# Sheet1.net
KiCad netlist of a schematic drawn in Altium Designer
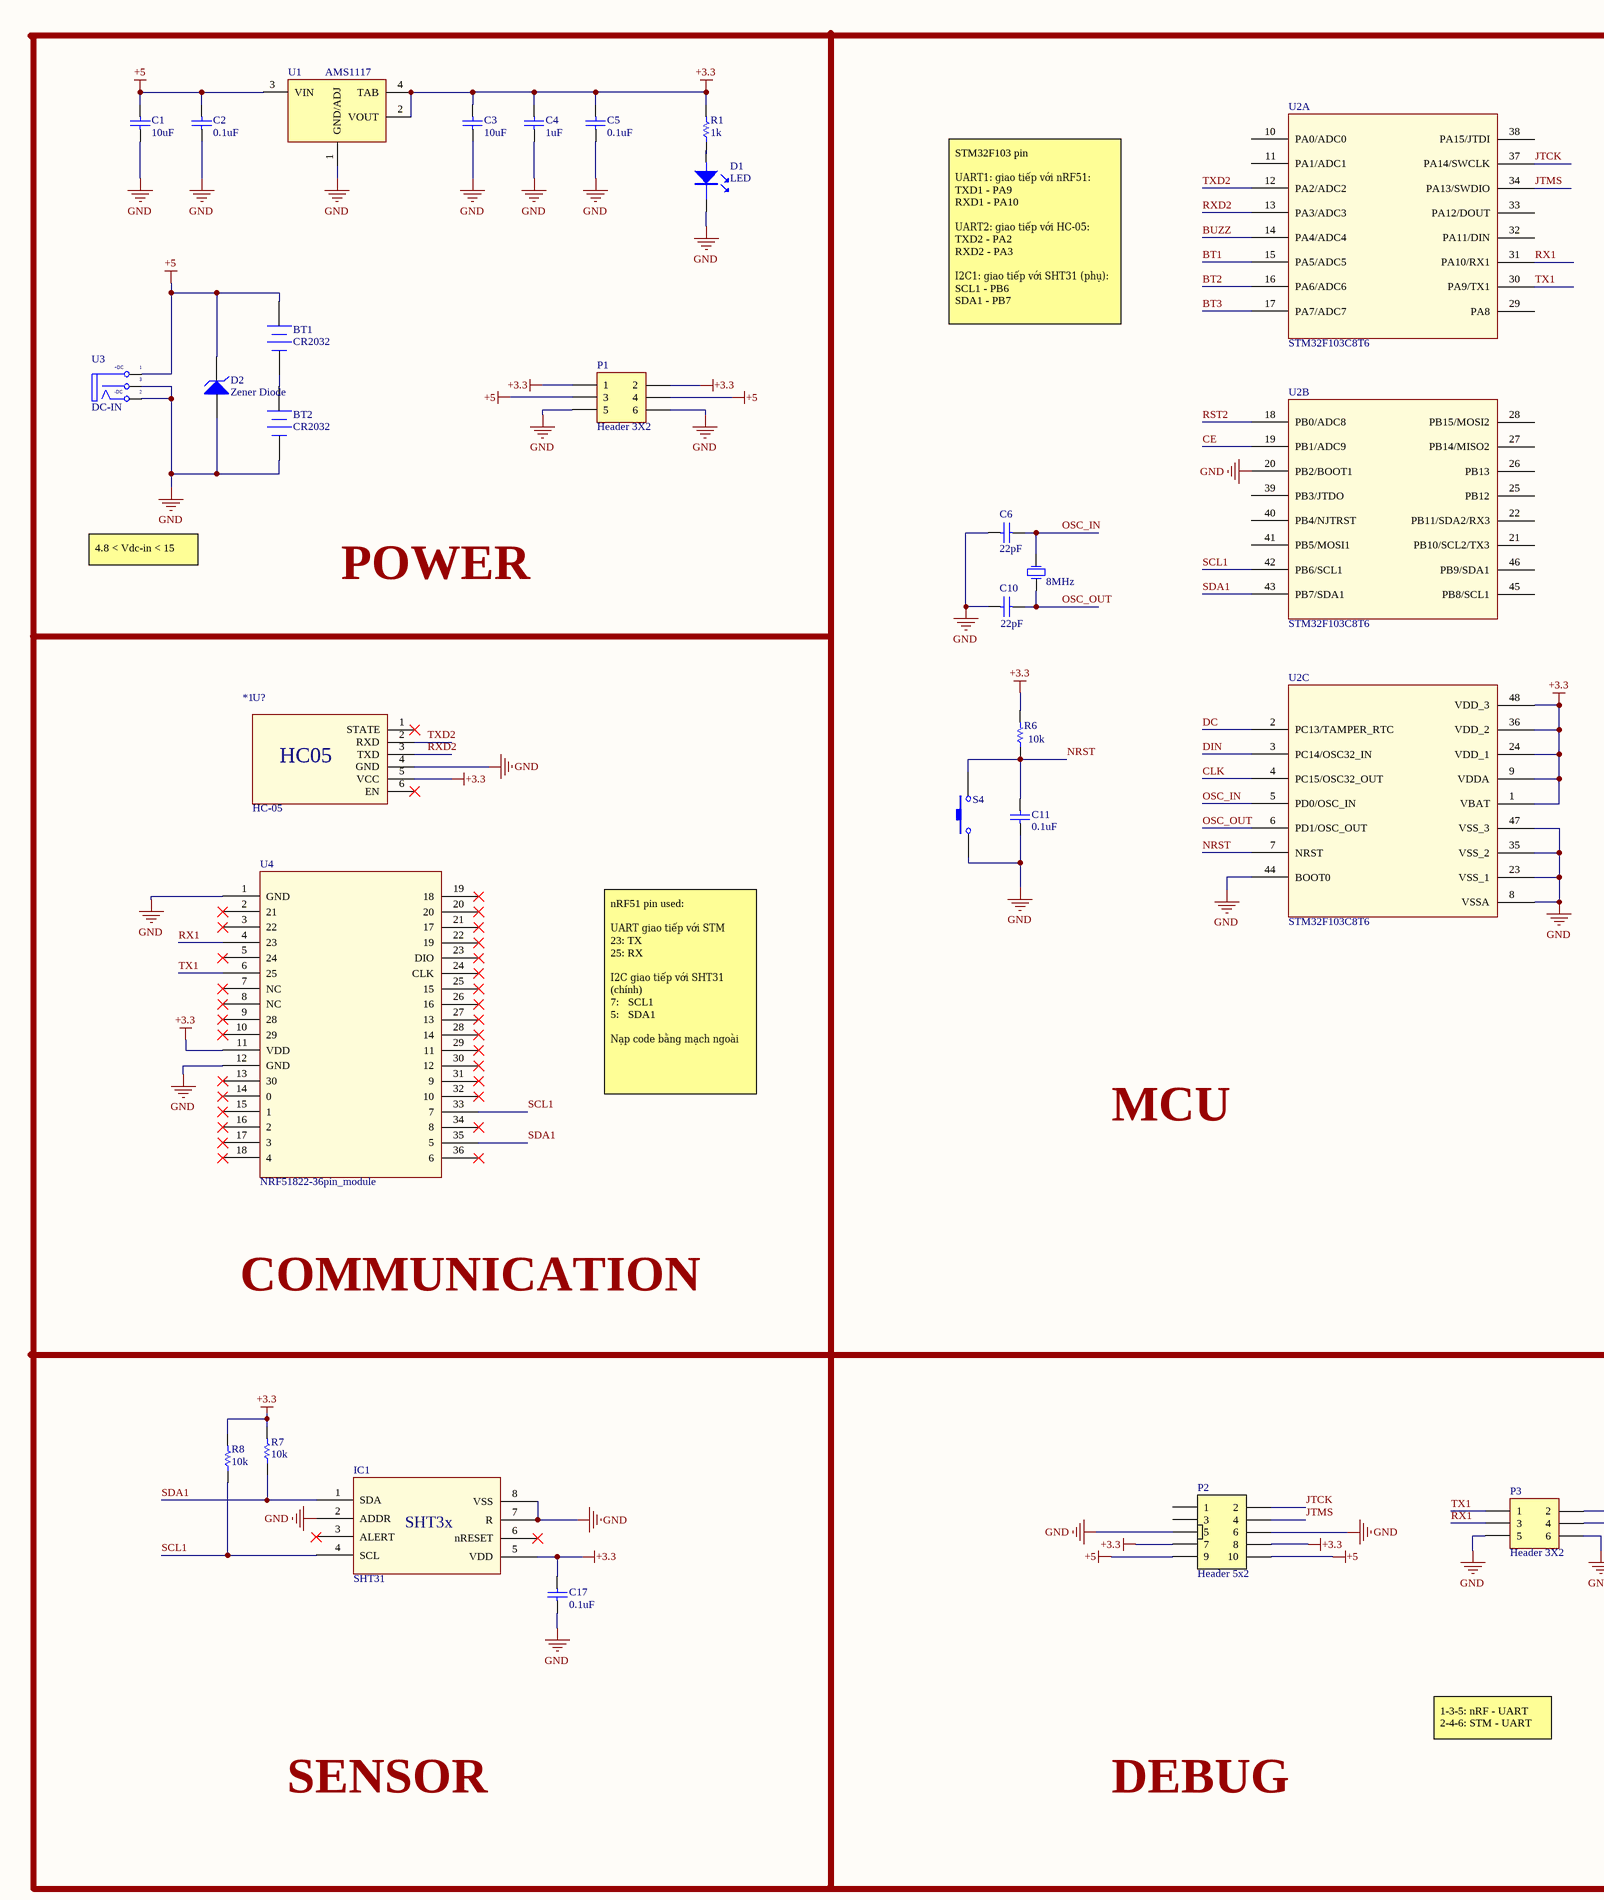
[diagram p0: Sheet1.SchDoc, left]
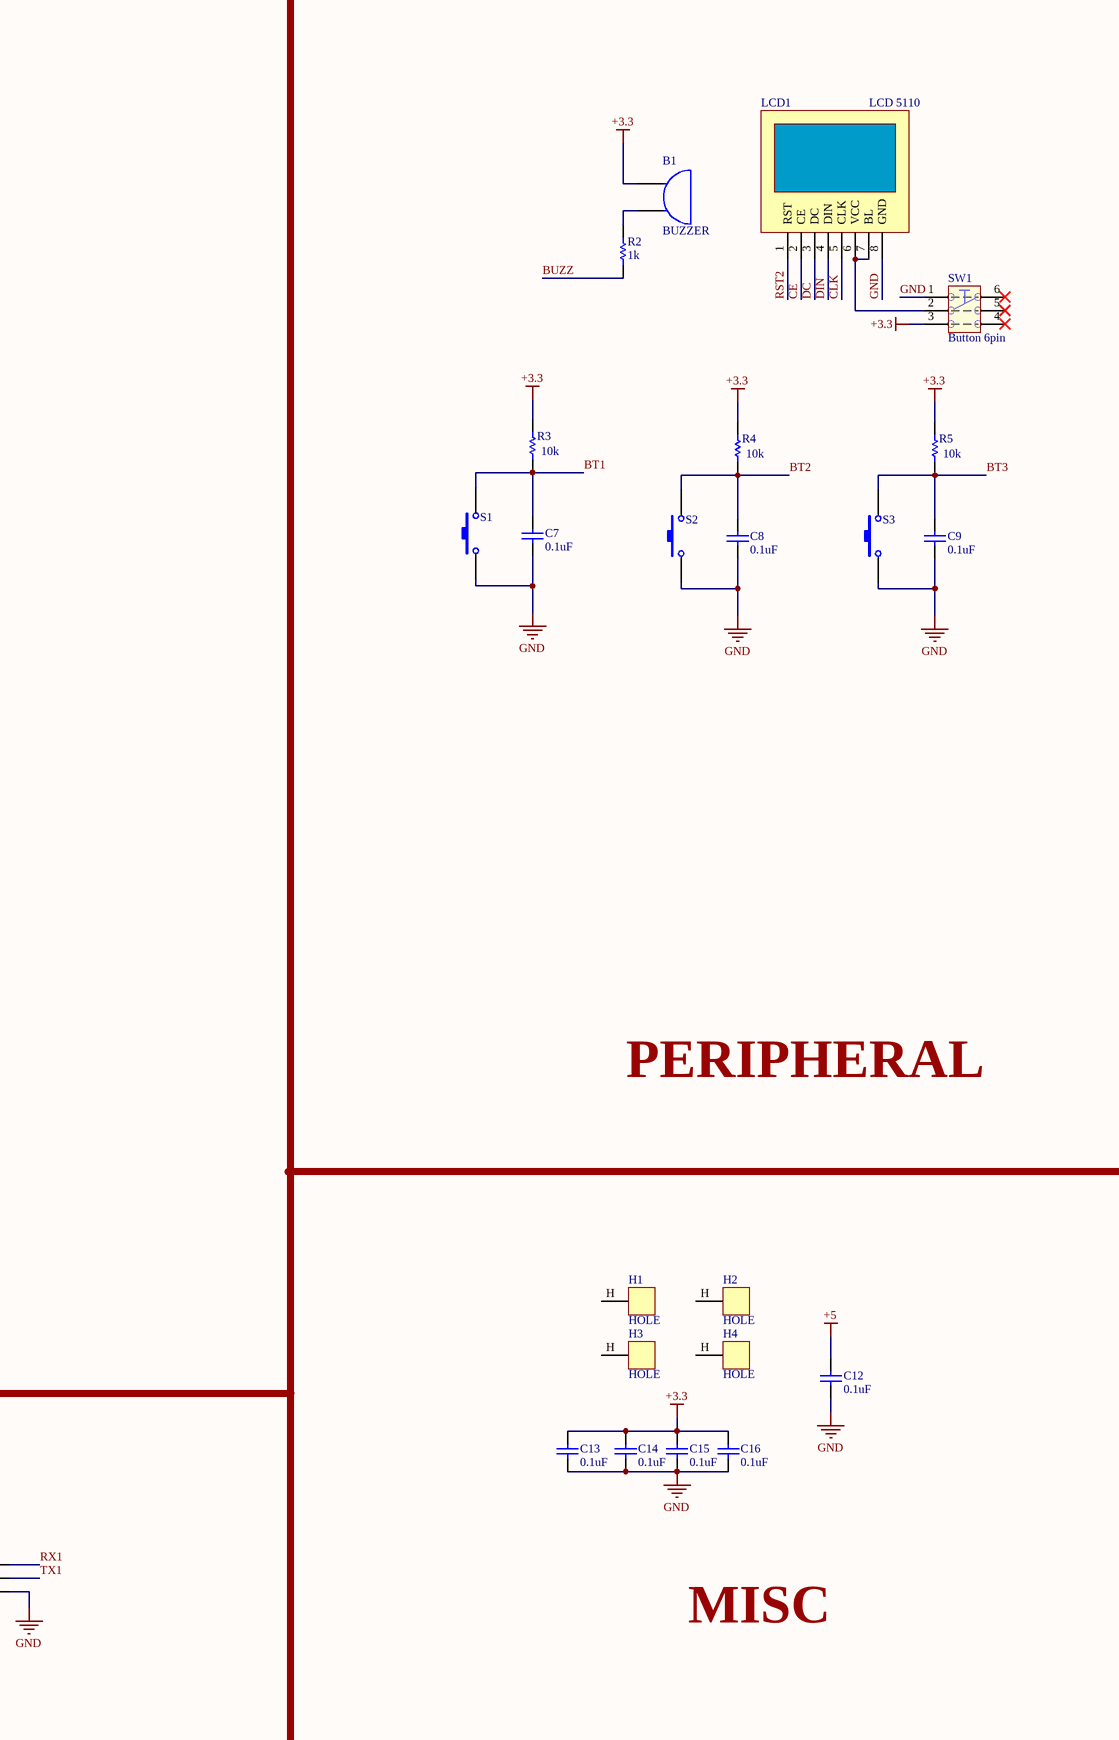
[diagram p1: Sheet1.SchDoc, right]

(export (version "E")
  (design (tool "Eeschema 10.0.6"))
  (components
    (comp (ref "*1") (value "HC-05") (footprint "HC-05") (libsource (lib "DucNam") (part "HC-05")))
    (comp (ref "B1")
      (value "BUZZER")
      (footprint "SPEAKER")
      (libsource (lib "ThinhNguyenLib") (part "BUZZER"))
    )
    (comp (ref "BT1")
      (value "CR2032")
      (footprint "PIN3V")
      (description "Multicell Battery")
      (fields (field (name "PUBLISHER") "Altium Limited"))
      (libsource (lib "DoHuong_sch") (part "Battery"))
    )
    (comp (ref "BT2")
      (value "CR2032")
      (footprint "PIN3V")
      (description "Multicell Battery")
      (fields (field (name "PUBLISHER") "Altium Limited"))
      (libsource (lib "DoHuong_sch") (part "Battery"))
    )
    (comp (ref "C1")
      (value "10uF")
      (footprint "C0805")
      (description "CAP CER 10UF 16V X7R 0805")
      (fields
        (field (name "PARTNUMBER") "EMK212BB7106MG-T")
        (field (name "TOLERANCE") "±20%")
        (field (name "CREATOR") "Quyen.nv")
      )
      (libsource (lib "MKP_lib") (part "CAP"))
    )
    (comp (ref "C2")
      (value "0.1uF")
      (footprint "C0805")
      (description "CAP CER 0.1UF 16V X7R 0805")
      (fields
        (field (name "PARTNUMBER") "C0805C104K4RACTU")
        (field (name "TOLERANCE") "±10%")
        (field (name "CREATOR") "Tunn")
      )
      (libsource (lib "MKP_lib") (part "CAP"))
    )
    (comp (ref "C3")
      (value "10uF")
      (footprint "C0805")
      (description "CAP CER 10UF 16V X7R 0805")
      (fields
        (field (name "PARTNUMBER") "EMK212BB7106MG-T")
        (field (name "TOLERANCE") "±20%")
        (field (name "CREATOR") "Quyen.nv")
      )
      (libsource (lib "MKP_lib") (part "CAP"))
    )
    (comp (ref "C4")
      (value "1uF")
      (footprint "C0805")
      (description "CAP CER 1UF 35V X7R 0805")
      (fields
        (field (name "PARTNUMBER") "GMK212B7105KG-T")
        (field (name "TOLERANCE") "±10%")
        (field (name "CREATOR") "Quyen.nv")
      )
      (libsource (lib "MKP_lib") (part "CAP"))
    )
    (comp (ref "C5")
      (value "0.1uF")
      (footprint "C0805")
      (description "CAP CER 0.1UF 16V X7R 0805")
      (fields
        (field (name "PARTNUMBER") "C0805C104K4RACTU")
        (field (name "TOLERANCE") "±10%")
        (field (name "CREATOR") "Tunn")
      )
      (libsource (lib "MKP_lib") (part "CAP"))
    )
    (comp (ref "C6")
      (value "22pF")
      (footprint "C0805")
      (description "CAP CER 0.22pF 0805")
      (fields
        (field (name "PARTNUMBER") "C0805C224K3RACAUTO")
        (field (name "TOLERANCE") "±10%")
        (field (name "CREATOR") "Quyen.nv")
      )
      (libsource (lib "MKP_lib") (part "CAP"))
    )
    (comp (ref "C7")
      (value "0.1uF")
      (footprint "C0805")
      (description "CAP CER 0.1UF 16V X7R 0805")
      (fields
        (field (name "PARTNUMBER") "C0805C104K4RACTU")
        (field (name "TOLERANCE") "±10%")
        (field (name "CREATOR") "Tunn")
      )
      (libsource (lib "MKP_lib") (part "CAP"))
    )
    (comp (ref "C8")
      (value "0.1uF")
      (footprint "C0805")
      (description "CAP CER 0.1UF 16V X7R 0805")
      (fields
        (field (name "PARTNUMBER") "C0805C104K4RACTU")
        (field (name "TOLERANCE") "±10%")
        (field (name "CREATOR") "Tunn")
      )
      (libsource (lib "MKP_lib") (part "CAP"))
    )
    (comp (ref "C9")
      (value "0.1uF")
      (footprint "C0805")
      (description "CAP CER 0.1UF 16V X7R 0805")
      (fields
        (field (name "PARTNUMBER") "C0805C104K4RACTU")
        (field (name "TOLERANCE") "±10%")
        (field (name "CREATOR") "Tunn")
      )
      (libsource (lib "MKP_lib") (part "CAP"))
    )
    (comp (ref "C10")
      (value "22pF")
      (footprint "C0805")
      (description "CAP CER 0.22pF 0805")
      (fields
        (field (name "PARTNUMBER") "C0805C224K3RACAUTO")
        (field (name "TOLERANCE") "±10%")
        (field (name "CREATOR") "Quyen.nv")
      )
      (libsource (lib "MKP_lib") (part "CAP"))
    )
    (comp (ref "C11")
      (value "0.1uF")
      (footprint "C0805")
      (description "CAP CER 0.1UF 16V X7R 0805")
      (fields
        (field (name "PARTNUMBER") "C0805C104K4RACTU")
        (field (name "TOLERANCE") "±10%")
        (field (name "CREATOR") "Tunn")
      )
      (libsource (lib "MKP_lib") (part "CAP"))
    )
    (comp (ref "C12")
      (value "0.1uF")
      (footprint "C0805")
      (description "CAP CER 0.1UF 16V X7R 0805")
      (fields
        (field (name "PARTNUMBER") "C0805C104K4RACTU")
        (field (name "TOLERANCE") "±10%")
        (field (name "CREATOR") "Tunn")
      )
      (libsource (lib "MKP_lib") (part "CAP"))
    )
    (comp (ref "C13")
      (value "0.1uF")
      (footprint "C0805")
      (description "CAP CER 0.1UF 16V X7R 0805")
      (fields
        (field (name "PARTNUMBER") "C0805C104K4RACTU")
        (field (name "TOLERANCE") "±10%")
        (field (name "CREATOR") "Tunn")
      )
      (libsource (lib "MKP_lib") (part "CAP"))
    )
    (comp (ref "C14")
      (value "0.1uF")
      (footprint "C0805")
      (description "CAP CER 0.1UF 16V X7R 0805")
      (fields
        (field (name "PARTNUMBER") "C0805C104K4RACTU")
        (field (name "TOLERANCE") "±10%")
        (field (name "CREATOR") "Tunn")
      )
      (libsource (lib "MKP_lib") (part "CAP"))
    )
    (comp (ref "C15")
      (value "0.1uF")
      (footprint "C0805")
      (description "CAP CER 0.1UF 16V X7R 0805")
      (fields
        (field (name "PARTNUMBER") "C0805C104K4RACTU")
        (field (name "TOLERANCE") "±10%")
        (field (name "CREATOR") "Tunn")
      )
      (libsource (lib "MKP_lib") (part "CAP"))
    )
    (comp (ref "C16")
      (value "0.1uF")
      (footprint "C0805")
      (description "CAP CER 0.1UF 16V X7R 0805")
      (fields
        (field (name "PARTNUMBER") "C0805C104K4RACTU")
        (field (name "TOLERANCE") "±10%")
        (field (name "CREATOR") "Tunn")
      )
      (libsource (lib "MKP_lib") (part "CAP"))
    )
    (comp (ref "C17")
      (value "0.1uF")
      (footprint "C0805")
      (description "CAP CER 0.1UF 16V X7R 0805")
      (fields
        (field (name "PARTNUMBER") "C0805C104K4RACTU")
        (field (name "TOLERANCE") "±10%")
        (field (name "CREATOR") "Tunn")
      )
      (libsource (lib "MKP_lib") (part "CAP"))
    )
    (comp (ref "D1") (value "LED") (footprint "LED SMD 0805") (libsource (lib "ThinhNguyenLib") (part "LED")))
    (comp (ref "D2")
      (value "Zener Diode")
      (footprint "Zener Diode")
      (description "General SCH for Zener Diode")
      (libsource (lib "DucNam") (part "Zener Diode"))
    )
    (comp (ref "H1") (value "HOLE") (footprint "HOLE") (libsource (lib "ThinhNguyenLib") (part "HOLE")))
    (comp (ref "H2") (value "HOLE") (footprint "HOLE") (libsource (lib "ThinhNguyenLib") (part "HOLE")))
    (comp (ref "H3") (value "HOLE") (footprint "HOLE") (libsource (lib "ThinhNguyenLib") (part "HOLE")))
    (comp (ref "H4") (value "HOLE") (footprint "HOLE") (libsource (lib "ThinhNguyenLib") (part "HOLE")))
    (comp (ref "IC1")
      (value "SHT31")
      (footprint "DFN-8")
      (description "Sensirion Humidity & Temperature Sensor")
      (libsource (lib "DucNam") (part "SHT31"))
    )
    (comp (ref "LCD1")
      (value "LCD 5110")
      (footprint "LCD 5110")
      (libsource (lib "ThinhNguyenLib") (part "LCD 5110"))
    )
    (comp (ref "P1")
      (value "Header 3X2")
      (footprint "HDR2X3")
      (description "Header, 3-Pin, Dual row")
      (fields (field (name "PUBLISHER") "Altium Limited"))
      (libsource (lib "DoHuong_sch") (part "Header 3X2"))
    )
    (comp (ref "P2")
      (value "Header 5x2")
      (footprint "Header 5x2 horizontal (2.54mm)")
      (description "Header 5x2 ,used for ST-Link")
      (libsource (lib "DucNam") (part "Header 5x2 (2.54mm)"))
    )
    (comp (ref "P3")
      (value "Header 3X2")
      (footprint "HDR2X3")
      (description "Header, 3-Pin, Dual row")
      (fields (field (name "PUBLISHER") "Altium Limited"))
      (libsource (lib "DoHuong_sch") (part "Header 3X2"))
    )
    (comp (ref "R1")
      (value "1k")
      (footprint "R0805")
      (description "RES SMD 100 OHM 1% 1/8W 0805")
      (fields
        (field (name "PARTNUMBER") "RC0805FR-07100RL")
        (field (name "TOLERANCE") "1%")
        (field (name "CREATOR") "Quyen.nv")
      )
      (libsource (lib "MKP_lib") (part "RES"))
    )
    (comp (ref "R2")
      (value "1k")
      (footprint "R0805")
      (description "RES SMD 100 OHM 1% 1/8W 0805")
      (fields
        (field (name "PARTNUMBER") "RC0805FR-07100RL")
        (field (name "TOLERANCE") "1%")
        (field (name "CREATOR") "Quyen.nv")
      )
      (libsource (lib "MKP_lib") (part "RES"))
    )
    (comp (ref "R3")
      (value "10k")
      (footprint "R0805")
      (description "RES SMD 100 OHM 1% 1/8W 0805")
      (fields
        (field (name "PARTNUMBER") "RC0805FR-07100RL")
        (field (name "TOLERANCE") "1%")
        (field (name "CREATOR") "Quyen.nv")
      )
      (libsource (lib "MKP_lib") (part "RES"))
    )
    (comp (ref "R4")
      (value "10k")
      (footprint "R0805")
      (description "RES SMD 100 OHM 1% 1/8W 0805")
      (fields
        (field (name "PARTNUMBER") "RC0805FR-07100RL")
        (field (name "TOLERANCE") "1%")
        (field (name "CREATOR") "Quyen.nv")
      )
      (libsource (lib "MKP_lib") (part "RES"))
    )
    (comp (ref "R5")
      (value "10k")
      (footprint "R0805")
      (description "RES SMD 100 OHM 1% 1/8W 0805")
      (fields
        (field (name "PARTNUMBER") "RC0805FR-07100RL")
        (field (name "TOLERANCE") "1%")
        (field (name "CREATOR") "Quyen.nv")
      )
      (libsource (lib "MKP_lib") (part "RES"))
    )
    (comp (ref "R6")
      (value "10k")
      (footprint "R0805")
      (description "RES SMD 100 OHM 1% 1/8W 0805")
      (fields
        (field (name "PARTNUMBER") "RC0805FR-07100RL")
        (field (name "TOLERANCE") "1%")
        (field (name "CREATOR") "Quyen.nv")
      )
      (libsource (lib "MKP_lib") (part "RES"))
    )
    (comp (ref "R7")
      (value "10k")
      (footprint "R0805")
      (description "RES SMD 100 OHM 1% 1/8W 0805")
      (fields
        (field (name "PARTNUMBER") "RC0805FR-07100RL")
        (field (name "TOLERANCE") "1%")
        (field (name "CREATOR") "Quyen.nv")
      )
      (libsource (lib "MKP_lib") (part "RES"))
    )
    (comp (ref "R8")
      (value "10k")
      (footprint "R0805")
      (description "RES SMD 100 OHM 1% 1/8W 0805")
      (fields
        (field (name "PARTNUMBER") "RC0805FR-07100RL")
        (field (name "TOLERANCE") "1%")
        (field (name "CREATOR") "Quyen.nv")
      )
      (libsource (lib "MKP_lib") (part "RES"))
    )
    (comp (ref "S1")
      (value "SWITCH")
      (footprint "SW 4PIN")
      (fields (field (name "PUBLISHER") "Altium Limited"))
      (libsource (lib "ThinhNguyenLib") (part "SWITCH"))
    )
    (comp (ref "S2")
      (value "SWITCH")
      (footprint "SW 4PIN")
      (fields (field (name "PUBLISHER") "Altium Limited"))
      (libsource (lib "ThinhNguyenLib") (part "SWITCH"))
    )
    (comp (ref "S3")
      (value "SWITCH")
      (footprint "SW 4PIN")
      (fields (field (name "PUBLISHER") "Altium Limited"))
      (libsource (lib "ThinhNguyenLib") (part "SWITCH"))
    )
    (comp (ref "S4")
      (value "SWITCH")
      (footprint "SW 4PIN")
      (fields (field (name "PUBLISHER") "Altium Limited"))
      (libsource (lib "ThinhNguyenLib") (part "SWITCH"))
    )
    (comp (ref "SW1")
      (value "Button 6pin")
      (footprint "BT 6pin")
      (description "General Pin 2, unpush 2-1 - push 2-3")
      (libsource (lib "DucNam") (part "Button 6-pin 2-state"))
    )
    (comp (ref "U1")
      (value "AMS1117")
      (footprint "SOT223 - 3 LEAD")
      (libsource (lib "ThinhNguyenLib") (part "AMS1117"))
    )
    (comp (ref "U2")
      (value "STM32F103C8T6")
      (footprint "LQFP48_7x7")
      (description "STM32F103C8T6-LQFP48")
      (libsource (lib "DucNam") (part "STM32F103C8T6-Multi-part"))
    )
    (comp (ref "U3")
      (value "DC-IN")
      (footprint "DC-IN")
      (description "Provide DC Voltage")
      (libsource (lib "DucNam") (part "JACK-DC"))
    )
    (comp (ref "U4")
      (value "NRF51822-36pin_module")
      (footprint "NRF51822_Module")
      (libsource (lib "DucNam") (part "NRF51822-Mudule"))
    )
    (comp (ref "Y1")
      (value "8MHz")
      (footprint "XTAL_HC-49/U")
      (description "Crystal Oscillator")
      (fields (field (name "PUBLISHER") "Altium Limited"))
      (libsource (lib "DoHuong_sch") (part "XTAL"))
    )
  )
  (nets
    (net (code "1") (name "+3.3") (class "Default")
      (node (ref "*1") (pin "5") (pinfunction "VCC_5") (pintype "passive"))
      (node (ref "B1") (pin "1") (pinfunction "A_1") (pintype "passive"))
      (node (ref "C13") (pin "2") (pinfunction "2_2") (pintype "passive"))
      (node (ref "C14") (pin "2") (pinfunction "2_2") (pintype "passive"))
      (node (ref "C15") (pin "2") (pinfunction "2_2") (pintype "passive"))
      (node (ref "C16") (pin "2") (pinfunction "2_2") (pintype "passive"))
      (node (ref "C17") (pin "2") (pinfunction "2_2") (pintype "passive"))
      (node (ref "C3") (pin "2") (pinfunction "2_2") (pintype "passive"))
      (node (ref "C4") (pin "1") (pinfunction "1_1") (pintype "passive"))
      (node (ref "C5") (pin "2") (pinfunction "2_2") (pintype "passive"))
      (node (ref "IC1") (pin "5") (pinfunction "VDD_5") (pintype "passive"))
      (node (ref "P1") (pin "1") (pinfunction "1_1") (pintype "passive"))
      (node (ref "P1") (pin "2") (pinfunction "2_2") (pintype "passive"))
      (node (ref "P2") (pin "7") (pinfunction "7_7") (pintype "passive"))
      (node (ref "P2") (pin "8") (pinfunction "8_8") (pintype "passive"))
      (node (ref "R1") (pin "1") (pinfunction "1_1") (pintype "passive"))
      (node (ref "R3") (pin "1") (pinfunction "1_1") (pintype "passive"))
      (node (ref "R4") (pin "1") (pinfunction "1_1") (pintype "passive"))
      (node (ref "R5") (pin "1") (pinfunction "1_1") (pintype "passive"))
      (node (ref "R6") (pin "1") (pinfunction "1_1") (pintype "passive"))
      (node (ref "R7") (pin "1") (pinfunction "1_1") (pintype "passive"))
      (node (ref "R8") (pin "1") (pinfunction "1_1") (pintype "passive"))
      (node (ref "SW1") (pin "3") (pinfunction "1_3") (pintype "passive"))
      (node (ref "U1") (pin "2") (pinfunction "VOUT_2") (pintype "passive"))
      (node (ref "U1") (pin "4") (pinfunction "TAB_4") (pintype "passive"))
      (node (ref "U2") (pin "1") (pinfunction "VBAT_1") (pintype "passive"))
      (node (ref "U2") (pin "24") (pinfunction "VDD_1_24") (pintype "passive"))
      (node (ref "U2") (pin "36") (pinfunction "VDD_2_36") (pintype "passive"))
      (node (ref "U2") (pin "48") (pinfunction "VDD_3_48") (pintype "passive"))
      (node (ref "U2") (pin "9") (pinfunction "VDDA_9") (pintype "passive"))
      (node (ref "U4") (pin "11") (pinfunction "VDD_11") (pintype "passive"))
    )
    (net (code "2") (name "+5") (class "Default")
      (node (ref "BT1") (pin "1") (pinfunction "+_1") (pintype "passive"))
      (node (ref "C1") (pin "2") (pinfunction "2_2") (pintype "passive"))
      (node (ref "C12") (pin "2") (pinfunction "2_2") (pintype "passive"))
      (node (ref "C2") (pin "2") (pinfunction "2_2") (pintype "passive"))
      (node (ref "D2") (pin "2") (pinfunction "K_2") (pintype "passive"))
      (node (ref "P1") (pin "3") (pinfunction "3_3") (pintype "passive"))
      (node (ref "P1") (pin "4") (pinfunction "4_4") (pintype "passive"))
      (node (ref "P2") (pin "10") (pinfunction "10_10") (pintype "passive"))
      (node (ref "P2") (pin "9") (pinfunction "9_9") (pintype "passive"))
      (node (ref "U1") (pin "3") (pinfunction "VIN_3") (pintype "passive"))
      (node (ref "U3") (pin "1") (pinfunction "T_1") (pintype "passive"))
    )
    (net (code "3") (name "/BT1") (class "Default")
      (node (ref "C7") (pin "2") (pinfunction "2_2") (pintype "passive"))
      (node (ref "R3") (pin "2") (pinfunction "2_2") (pintype "passive"))
      (node (ref "S1") (pin "2") (pinfunction "2_2") (pintype "passive"))
      (node (ref "U2") (pin "15") (pinfunction "PA5/ADC5_15") (pintype "passive"))
    )
    (net (code "4") (name "/BT2") (class "Default")
      (node (ref "C8") (pin "2") (pinfunction "2_2") (pintype "passive"))
      (node (ref "R4") (pin "2") (pinfunction "2_2") (pintype "passive"))
      (node (ref "S2") (pin "2") (pinfunction "2_2") (pintype "passive"))
      (node (ref "U2") (pin "16") (pinfunction "PA6/ADC6_16") (pintype "passive"))
    )
    (net (code "5") (name "/BT3") (class "Default")
      (node (ref "C9") (pin "2") (pinfunction "2_2") (pintype "passive"))
      (node (ref "R5") (pin "2") (pinfunction "2_2") (pintype "passive"))
      (node (ref "S3") (pin "2") (pinfunction "2_2") (pintype "passive"))
      (node (ref "U2") (pin "17") (pinfunction "PA7/ADC7_17") (pintype "passive"))
    )
    (net (code "6") (name "/BUZZ") (class "Default")
      (node (ref "R2") (pin "2") (pinfunction "2_2") (pintype "passive"))
      (node (ref "U2") (pin "14") (pinfunction "PA4/ADC4_14") (pintype "passive"))
    )
    (net (code "7") (name "/CE") (class "Default")
      (node (ref "LCD1") (pin "2") (pinfunction "CE_2") (pintype "passive"))
      (node (ref "U2") (pin "19") (pinfunction "PB1/ADC9_19") (pintype "passive"))
    )
    (net (code "8") (name "/CLK") (class "Default")
      (node (ref "LCD1") (pin "5") (pinfunction "CLK_5") (pintype "passive"))
      (node (ref "U2") (pin "4") (pinfunction "PC15/OSC32_OUT_4") (pintype "passive"))
    )
    (net (code "9") (name "/DC") (class "Default")
      (node (ref "LCD1") (pin "3") (pinfunction "DC_3") (pintype "passive"))
      (node (ref "U2") (pin "2") (pinfunction "PC13/TAMPER_RTC_2") (pintype "passive"))
    )
    (net (code "10") (name "/DIN") (class "Default")
      (node (ref "LCD1") (pin "4") (pinfunction "DIN_4") (pintype "passive"))
      (node (ref "U2") (pin "3") (pinfunction "PC14/OSC32_IN_3") (pintype "passive"))
    )
    (net (code "11") (name "/JTCK") (class "Default")
      (node (ref "P2") (pin "2") (pinfunction "2_2") (pintype "passive"))
      (node (ref "U2") (pin "37") (pinfunction "PA14/SWCLK_37") (pintype "passive"))
    )
    (net (code "12") (name "/JTMS") (class "Default")
      (node (ref "P2") (pin "4") (pinfunction "4_4") (pintype "passive"))
      (node (ref "U2") (pin "34") (pinfunction "PA13/SWDIO_34") (pintype "passive"))
    )
    (net (code "13") (name "/NRST") (class "Default")
      (node (ref "C11") (pin "2") (pinfunction "2_2") (pintype "passive"))
      (node (ref "R6") (pin "2") (pinfunction "2_2") (pintype "passive"))
      (node (ref "S4") (pin "2") (pinfunction "2_2") (pintype "passive"))
      (node (ref "U2") (pin "7") (pinfunction "NRST_7") (pintype "passive"))
    )
    (net (code "14") (name "/OSC_IN") (class "Default")
      (node (ref "C6") (pin "2") (pinfunction "2_2") (pintype "passive"))
      (node (ref "U2") (pin "5") (pinfunction "PD0/OSC_IN_5") (pintype "passive"))
      (node (ref "Y1") (pin "2") (pinfunction "OSC2_2") (pintype "passive"))
    )
    (net (code "15") (name "/OSC_OUT") (class "Default")
      (node (ref "C10") (pin "2") (pinfunction "2_2") (pintype "passive"))
      (node (ref "U2") (pin "6") (pinfunction "PD1/OSC_OUT_6") (pintype "passive"))
      (node (ref "Y1") (pin "1") (pinfunction "OSC1_1") (pintype "passive"))
    )
    (net (code "16") (name "/RST2") (class "Default")
      (node (ref "LCD1") (pin "1") (pinfunction "RST_1") (pintype "passive"))
      (node (ref "U2") (pin "18") (pinfunction "PB0/ADC8_18") (pintype "passive"))
    )
    (net (code "17") (name "/RX1") (class "Default")
      (node (ref "P3") (pin "2") (pinfunction "2_2") (pintype "passive"))
      (node (ref "P3") (pin "3") (pinfunction "3_3") (pintype "passive"))
      (node (ref "U2") (pin "31") (pinfunction "PA10/RX1_31") (pintype "passive"))
      (node (ref "U4") (pin "4") (pinfunction "23_4") (pintype "passive"))
    )
    (net (code "18") (name "/RXD2") (class "Default")
      (node (ref "*1") (pin "3") (pinfunction "TXD_3") (pintype "passive"))
      (node (ref "U2") (pin "13") (pinfunction "PA3/ADC3_13") (pintype "passive"))
    )
    (net (code "19") (name "/SCL1") (class "Default")
      (node (ref "IC1") (pin "4") (pinfunction "SCL_4") (pintype "passive"))
      (node (ref "R8") (pin "2") (pinfunction "2_2") (pintype "passive"))
      (node (ref "U2") (pin "42") (pinfunction "PB6/SCL1_42") (pintype "passive"))
      (node (ref "U4") (pin "33") (pinfunction "7_33") (pintype "passive"))
    )
    (net (code "20") (name "/SDA1") (class "Default")
      (node (ref "IC1") (pin "1") (pinfunction "SDA_1") (pintype "passive"))
      (node (ref "R7") (pin "2") (pinfunction "2_2") (pintype "passive"))
      (node (ref "U2") (pin "43") (pinfunction "PB7/SDA1_43") (pintype "passive"))
      (node (ref "U4") (pin "35") (pinfunction "5_35") (pintype "passive"))
    )
    (net (code "21") (name "/TX1") (class "Default")
      (node (ref "P3") (pin "1") (pinfunction "1_1") (pintype "passive"))
      (node (ref "P3") (pin "4") (pinfunction "4_4") (pintype "passive"))
      (node (ref "U2") (pin "30") (pinfunction "PA9/TX1_30") (pintype "passive"))
      (node (ref "U4") (pin "6") (pinfunction "25_6") (pintype "passive"))
    )
    (net (code "22") (name "/TXD2") (class "Default")
      (node (ref "*1") (pin "2") (pinfunction "RXD_2") (pintype "passive"))
      (node (ref "U2") (pin "12") (pinfunction "PA2/ADC2_12") (pintype "passive"))
    )
    (net (code "23") (name "GND") (class "Default")
      (node (ref "*1") (pin "4") (pinfunction "GND_4") (pintype "passive"))
      (node (ref "BT2") (pin "2") (pinfunction "-_2") (pintype "passive"))
      (node (ref "C1") (pin "1") (pinfunction "1_1") (pintype "passive"))
      (node (ref "C10") (pin "1") (pinfunction "1_1") (pintype "passive"))
      (node (ref "C11") (pin "1") (pinfunction "1_1") (pintype "passive"))
      (node (ref "C12") (pin "1") (pinfunction "1_1") (pintype "passive"))
      (node (ref "C13") (pin "1") (pinfunction "1_1") (pintype "passive"))
      (node (ref "C14") (pin "1") (pinfunction "1_1") (pintype "passive"))
      (node (ref "C15") (pin "1") (pinfunction "1_1") (pintype "passive"))
      (node (ref "C16") (pin "1") (pinfunction "1_1") (pintype "passive"))
      (node (ref "C17") (pin "1") (pinfunction "1_1") (pintype "passive"))
      (node (ref "C2") (pin "1") (pinfunction "1_1") (pintype "passive"))
      (node (ref "C3") (pin "1") (pinfunction "1_1") (pintype "passive"))
      (node (ref "C4") (pin "2") (pinfunction "2_2") (pintype "passive"))
      (node (ref "C5") (pin "1") (pinfunction "1_1") (pintype "passive"))
      (node (ref "C6") (pin "1") (pinfunction "1_1") (pintype "passive"))
      (node (ref "C7") (pin "1") (pinfunction "1_1") (pintype "passive"))
      (node (ref "C8") (pin "1") (pinfunction "1_1") (pintype "passive"))
      (node (ref "C9") (pin "1") (pinfunction "1_1") (pintype "passive"))
      (node (ref "D1") (pin "2") (pinfunction "2_2") (pintype "passive"))
      (node (ref "D2") (pin "1") (pinfunction "A_1") (pintype "passive"))
      (node (ref "IC1") (pin "2") (pinfunction "ADDR_2") (pintype "passive"))
      (node (ref "IC1") (pin "7") (pinfunction "R_7") (pintype "passive"))
      (node (ref "IC1") (pin "8") (pinfunction "VSS_8") (pintype "passive"))
      (node (ref "LCD1") (pin "8") (pinfunction "GND_8") (pintype "passive"))
      (node (ref "P1") (pin "5") (pinfunction "5_5") (pintype "passive"))
      (node (ref "P1") (pin "6") (pinfunction "6_6") (pintype "passive"))
      (node (ref "P2") (pin "5") (pinfunction "5_5") (pintype "passive"))
      (node (ref "P2") (pin "6") (pinfunction "6_6") (pintype "passive"))
      (node (ref "P3") (pin "5") (pinfunction "5_5") (pintype "passive"))
      (node (ref "P3") (pin "6") (pinfunction "6_6") (pintype "passive"))
      (node (ref "S1") (pin "1") (pinfunction "1_1") (pintype "passive"))
      (node (ref "S2") (pin "1") (pinfunction "1_1") (pintype "passive"))
      (node (ref "S3") (pin "1") (pinfunction "1_1") (pintype "passive"))
      (node (ref "S4") (pin "1") (pinfunction "1_1") (pintype "passive"))
      (node (ref "SW1") (pin "1") (pinfunction "3_1") (pintype "passive"))
      (node (ref "U1") (pin "1") (pinfunction "GND/ADJ_1") (pintype "passive"))
      (node (ref "U2") (pin "20") (pinfunction "PB2/BOOT1_20") (pintype "passive"))
      (node (ref "U2") (pin "23") (pinfunction "VSS_1_23") (pintype "passive"))
      (node (ref "U2") (pin "35") (pinfunction "VSS_2_35") (pintype "passive"))
      (node (ref "U2") (pin "44") (pinfunction "BOOT0_44") (pintype "passive"))
      (node (ref "U2") (pin "47") (pinfunction "VSS_3_47") (pintype "passive"))
      (node (ref "U2") (pin "8") (pinfunction "VSSA_8") (pintype "passive"))
      (node (ref "U3") (pin "2") (pinfunction "TN_2") (pintype "passive"))
      (node (ref "U3") (pin "3") (pinfunction "S_3") (pintype "power_in"))
      (node (ref "U4") (pin "1") (pinfunction "GND_1") (pintype "passive"))
      (node (ref "U4") (pin "12") (pinfunction "GND_12") (pintype "passive"))
    )
    (net (code "24") (name "Net-(B1-B)") (class "Default")
      (node (ref "B1") (pin "2") (pinfunction "B_2") (pintype "passive"))
      (node (ref "R2") (pin "1") (pinfunction "1_1") (pintype "passive"))
    )
    (net (code "25") (name "Net-(BT1--)") (class "Default")
      (node (ref "BT1") (pin "2") (pinfunction "-_2") (pintype "passive"))
      (node (ref "BT2") (pin "1") (pinfunction "+_1") (pintype "passive"))
    )
    (net (code "26") (name "Net-(D1-Pad1)") (class "Default")
      (node (ref "D1") (pin "1") (pinfunction "1_1") (pintype "passive"))
      (node (ref "R1") (pin "2") (pinfunction "2_2") (pintype "passive"))
    )
    (net (code "27") (name "Net-(LCD1-BL)") (class "Default")
      (node (ref "LCD1") (pin "6") (pinfunction "VCC_6") (pintype "passive"))
      (node (ref "LCD1") (pin "7") (pinfunction "BL_7") (pintype "passive"))
      (node (ref "SW1") (pin "2") (pinfunction "2_2") (pintype "passive"))
    )
    (net (code "28") (name "unconnected-(*1-EN-Pad6)") (class "Default")
      (node (ref "*1") (pin "6") (pinfunction "EN_6") (pintype "passive+no_connect"))
    )
    (net (code "29") (name "unconnected-(*1-STATE-Pad1)") (class "Default")
      (node (ref "*1") (pin "1") (pinfunction "STATE_1") (pintype "passive+no_connect"))
    )
    (net (code "30") (name "unconnected-(H1-HOLE-PadH)") (class "Default")
      (node (ref "H1") (pin "H") (pinfunction "HOLE_H") (pintype "passive"))
    )
    (net (code "31") (name "unconnected-(H2-HOLE-PadH)") (class "Default")
      (node (ref "H2") (pin "H") (pinfunction "HOLE_H") (pintype "passive"))
    )
    (net (code "32") (name "unconnected-(H3-HOLE-PadH)") (class "Default")
      (node (ref "H3") (pin "H") (pinfunction "HOLE_H") (pintype "passive"))
    )
    (net (code "33") (name "unconnected-(H4-HOLE-PadH)") (class "Default")
      (node (ref "H4") (pin "H") (pinfunction "HOLE_H") (pintype "passive"))
    )
    (net (code "34") (name "unconnected-(IC1-ALERT-Pad3)") (class "Default")
      (node (ref "IC1") (pin "3") (pinfunction "ALERT_3") (pintype "passive+no_connect"))
    )
    (net (code "35") (name "unconnected-(IC1-nRESET-Pad6)") (class "Default")
      (node (ref "IC1") (pin "6") (pinfunction "nRESET_6") (pintype "passive+no_connect"))
    )
    (net (code "36") (name "unconnected-(P2-Pad1)") (class "Default")
      (node (ref "P2") (pin "1") (pinfunction "1_1") (pintype "passive"))
    )
    (net (code "37") (name "unconnected-(P2-Pad3)") (class "Default")
      (node (ref "P2") (pin "3") (pinfunction "3_3") (pintype "passive"))
    )
    (net (code "38") (name "unconnected-(SW1-1-Pad6)") (class "Default")
      (node (ref "SW1") (pin "6") (pinfunction "1_6") (pintype "passive+no_connect"))
    )
    (net (code "39") (name "unconnected-(SW1-2-Pad5)") (class "Default")
      (node (ref "SW1") (pin "5") (pinfunction "2_5") (pintype "passive+no_connect"))
    )
    (net (code "40") (name "unconnected-(SW1-3-Pad4)") (class "Default")
      (node (ref "SW1") (pin "4") (pinfunction "3_4") (pintype "passive+no_connect"))
    )
    (net (code "41") (name "unconnected-(U2A-PA0{slash}ADC0-Pad10)") (class "Default")
      (node (ref "U2") (pin "10") (pinfunction "PA0/ADC0_10") (pintype "passive"))
    )
    (net (code "42") (name "unconnected-(U2A-PA1{slash}ADC1-Pad11)") (class "Default")
      (node (ref "U2") (pin "11") (pinfunction "PA1/ADC1_11") (pintype "passive"))
    )
    (net (code "43") (name "unconnected-(U2A-PA8-Pad29)") (class "Default")
      (node (ref "U2") (pin "29") (pinfunction "PA8_29") (pintype "passive"))
    )
    (net (code "44") (name "unconnected-(U2A-PA11{slash}DIN-Pad32)") (class "Default")
      (node (ref "U2") (pin "32") (pinfunction "PA11/DIN_32") (pintype "passive"))
    )
    (net (code "45") (name "unconnected-(U2A-PA12{slash}DOUT-Pad33)") (class "Default")
      (node (ref "U2") (pin "33") (pinfunction "PA12/DOUT_33") (pintype "passive"))
    )
    (net (code "46") (name "unconnected-(U2A-PA15{slash}JTDI-Pad38)") (class "Default")
      (node (ref "U2") (pin "38") (pinfunction "PA15/JTDI_38") (pintype "passive"))
    )
    (net (code "47") (name "unconnected-(U2B-PB3{slash}JTDO-Pad39)") (class "Default")
      (node (ref "U2") (pin "39") (pinfunction "PB3/JTDO_39") (pintype "passive"))
    )
    (net (code "48") (name "unconnected-(U2B-PB4{slash}NJTRST-Pad40)") (class "Default")
      (node (ref "U2") (pin "40") (pinfunction "PB4/NJTRST_40") (pintype "passive"))
    )
    (net (code "49") (name "unconnected-(U2B-PB5{slash}MOSI1-Pad41)") (class "Default")
      (node (ref "U2") (pin "41") (pinfunction "PB5/MOSI1_41") (pintype "passive"))
    )
    (net (code "50") (name "unconnected-(U2B-PB8{slash}SCL1-Pad45)") (class "Default")
      (node (ref "U2") (pin "45") (pinfunction "PB8/SCL1_45") (pintype "passive"))
    )
    (net (code "51") (name "unconnected-(U2B-PB9{slash}SDA1-Pad46)") (class "Default")
      (node (ref "U2") (pin "46") (pinfunction "PB9/SDA1_46") (pintype "passive"))
    )
    (net (code "52") (name "unconnected-(U2B-PB10{slash}SCL2{slash}TX3-Pad21)") (class "Default")
      (node (ref "U2") (pin "21") (pinfunction "PB10/SCL2/TX3_21") (pintype "passive"))
    )
    (net (code "53") (name "unconnected-(U2B-PB11{slash}SDA2{slash}RX3-Pad22)") (class "Default")
      (node (ref "U2") (pin "22") (pinfunction "PB11/SDA2/RX3_22") (pintype "passive"))
    )
    (net (code "54") (name "unconnected-(U2B-PB12-Pad25)") (class "Default")
      (node (ref "U2") (pin "25") (pinfunction "PB12_25") (pintype "passive"))
    )
    (net (code "55") (name "unconnected-(U2B-PB13-Pad26)") (class "Default")
      (node (ref "U2") (pin "26") (pinfunction "PB13_26") (pintype "passive"))
    )
    (net (code "56") (name "unconnected-(U2B-PB14{slash}MISO2-Pad27)") (class "Default")
      (node (ref "U2") (pin "27") (pinfunction "PB14/MISO2_27") (pintype "passive"))
    )
    (net (code "57") (name "unconnected-(U2B-PB15{slash}MOSI2-Pad28)") (class "Default")
      (node (ref "U2") (pin "28") (pinfunction "PB15/MOSI2_28") (pintype "passive"))
    )
    (net (code "58") (name "unconnected-(U4-0-Pad14)") (class "Default")
      (node (ref "U4") (pin "14") (pinfunction "0_14") (pintype "passive+no_connect"))
    )
    (net (code "59") (name "unconnected-(U4-1-Pad15)") (class "Default")
      (node (ref "U4") (pin "15") (pinfunction "1_15") (pintype "passive+no_connect"))
    )
    (net (code "60") (name "unconnected-(U4-2-Pad16)") (class "Default")
      (node (ref "U4") (pin "16") (pinfunction "2_16") (pintype "passive+no_connect"))
    )
    (net (code "61") (name "unconnected-(U4-3-Pad17)") (class "Default")
      (node (ref "U4") (pin "17") (pinfunction "3_17") (pintype "passive+no_connect"))
    )
    (net (code "62") (name "unconnected-(U4-4-Pad18)") (class "Default")
      (node (ref "U4") (pin "18") (pinfunction "4_18") (pintype "passive+no_connect"))
    )
    (net (code "63") (name "unconnected-(U4-6-Pad36)") (class "Default")
      (node (ref "U4") (pin "36") (pinfunction "6_36") (pintype "passive+no_connect"))
    )
    (net (code "64") (name "unconnected-(U4-8-Pad34)") (class "Default")
      (node (ref "U4") (pin "34") (pinfunction "8_34") (pintype "passive+no_connect"))
    )
    (net (code "65") (name "unconnected-(U4-9-Pad31)") (class "Default")
      (node (ref "U4") (pin "31") (pinfunction "9_31") (pintype "passive+no_connect"))
    )
    (net (code "66") (name "unconnected-(U4-10-Pad32)") (class "Default")
      (node (ref "U4") (pin "32") (pinfunction "10_32") (pintype "passive+no_connect"))
    )
    (net (code "67") (name "unconnected-(U4-11-Pad29)") (class "Default")
      (node (ref "U4") (pin "29") (pinfunction "11_29") (pintype "passive+no_connect"))
    )
    (net (code "68") (name "unconnected-(U4-12-Pad30)") (class "Default")
      (node (ref "U4") (pin "30") (pinfunction "12_30") (pintype "passive+no_connect"))
    )
    (net (code "69") (name "unconnected-(U4-13-Pad27)") (class "Default")
      (node (ref "U4") (pin "27") (pinfunction "13_27") (pintype "passive+no_connect"))
    )
    (net (code "70") (name "unconnected-(U4-14-Pad28)") (class "Default")
      (node (ref "U4") (pin "28") (pinfunction "14_28") (pintype "passive+no_connect"))
    )
    (net (code "71") (name "unconnected-(U4-15-Pad25)") (class "Default")
      (node (ref "U4") (pin "25") (pinfunction "15_25") (pintype "passive+no_connect"))
    )
    (net (code "72") (name "unconnected-(U4-16-Pad26)") (class "Default")
      (node (ref "U4") (pin "26") (pinfunction "16_26") (pintype "passive+no_connect"))
    )
    (net (code "73") (name "unconnected-(U4-17-Pad21)") (class "Default")
      (node (ref "U4") (pin "21") (pinfunction "17_21") (pintype "passive+no_connect"))
    )
    (net (code "74") (name "unconnected-(U4-18-Pad19)") (class "Default")
      (node (ref "U4") (pin "19") (pinfunction "18_19") (pintype "passive+no_connect"))
    )
    (net (code "75") (name "unconnected-(U4-19-Pad22)") (class "Default")
      (node (ref "U4") (pin "22") (pinfunction "19_22") (pintype "passive+no_connect"))
    )
    (net (code "76") (name "unconnected-(U4-21-Pad2)") (class "Default")
      (node (ref "U4") (pin "2") (pinfunction "21_2") (pintype "passive+no_connect"))
    )
    (net (code "77") (name "unconnected-(U4-22-Pad3)") (class "Default")
      (node (ref "U4") (pin "3") (pinfunction "22_3") (pintype "passive+no_connect"))
    )
    (net (code "78") (name "unconnected-(U4-24-Pad5)") (class "Default")
      (node (ref "U4") (pin "5") (pinfunction "24_5") (pintype "passive+no_connect"))
    )
    (net (code "79") (name "unconnected-(U4-28-Pad9)") (class "Default")
      (node (ref "U4") (pin "9") (pinfunction "28_9") (pintype "passive+no_connect"))
    )
    (net (code "80") (name "unconnected-(U4-29-Pad10)") (class "Default")
      (node (ref "U4") (pin "10") (pinfunction "29_10") (pintype "passive+no_connect"))
    )
    (net (code "81") (name "unconnected-(U4-30-Pad13)") (class "Default")
      (node (ref "U4") (pin "13") (pinfunction "30_13") (pintype "passive+no_connect"))
    )
    (net (code "82") (name "unconnected-(U4-CLK-Pad24)") (class "Default")
      (node (ref "U4") (pin "24") (pinfunction "CLK_24") (pintype "passive+no_connect"))
    )
    (net (code "83") (name "unconnected-(U4-DIO-Pad23)") (class "Default")
      (node (ref "U4") (pin "23") (pinfunction "DIO_23") (pintype "passive+no_connect"))
    )
    (net (code "84") (name "unconnected-(U4-NC-Pad7)") (class "Default")
      (node (ref "U4") (pin "7") (pinfunction "NC_7") (pintype "passive+no_connect"))
    )
    (net (code "85") (name "unconnected-(U4-NC-Pad8)") (class "Default")
      (node (ref "U4") (pin "8") (pinfunction "NC_8") (pintype "passive+no_connect"))
    )
    (net (code "86") (name "unconnected-(U4-Pad20)") (class "Default")
      (node (ref "U4") (pin "20") (pinfunction "20_20") (pintype "passive+no_connect"))
    )
  )
)
